# P08_PHY_3.net
KiCad netlist of a schematic drawn in Altium Designer
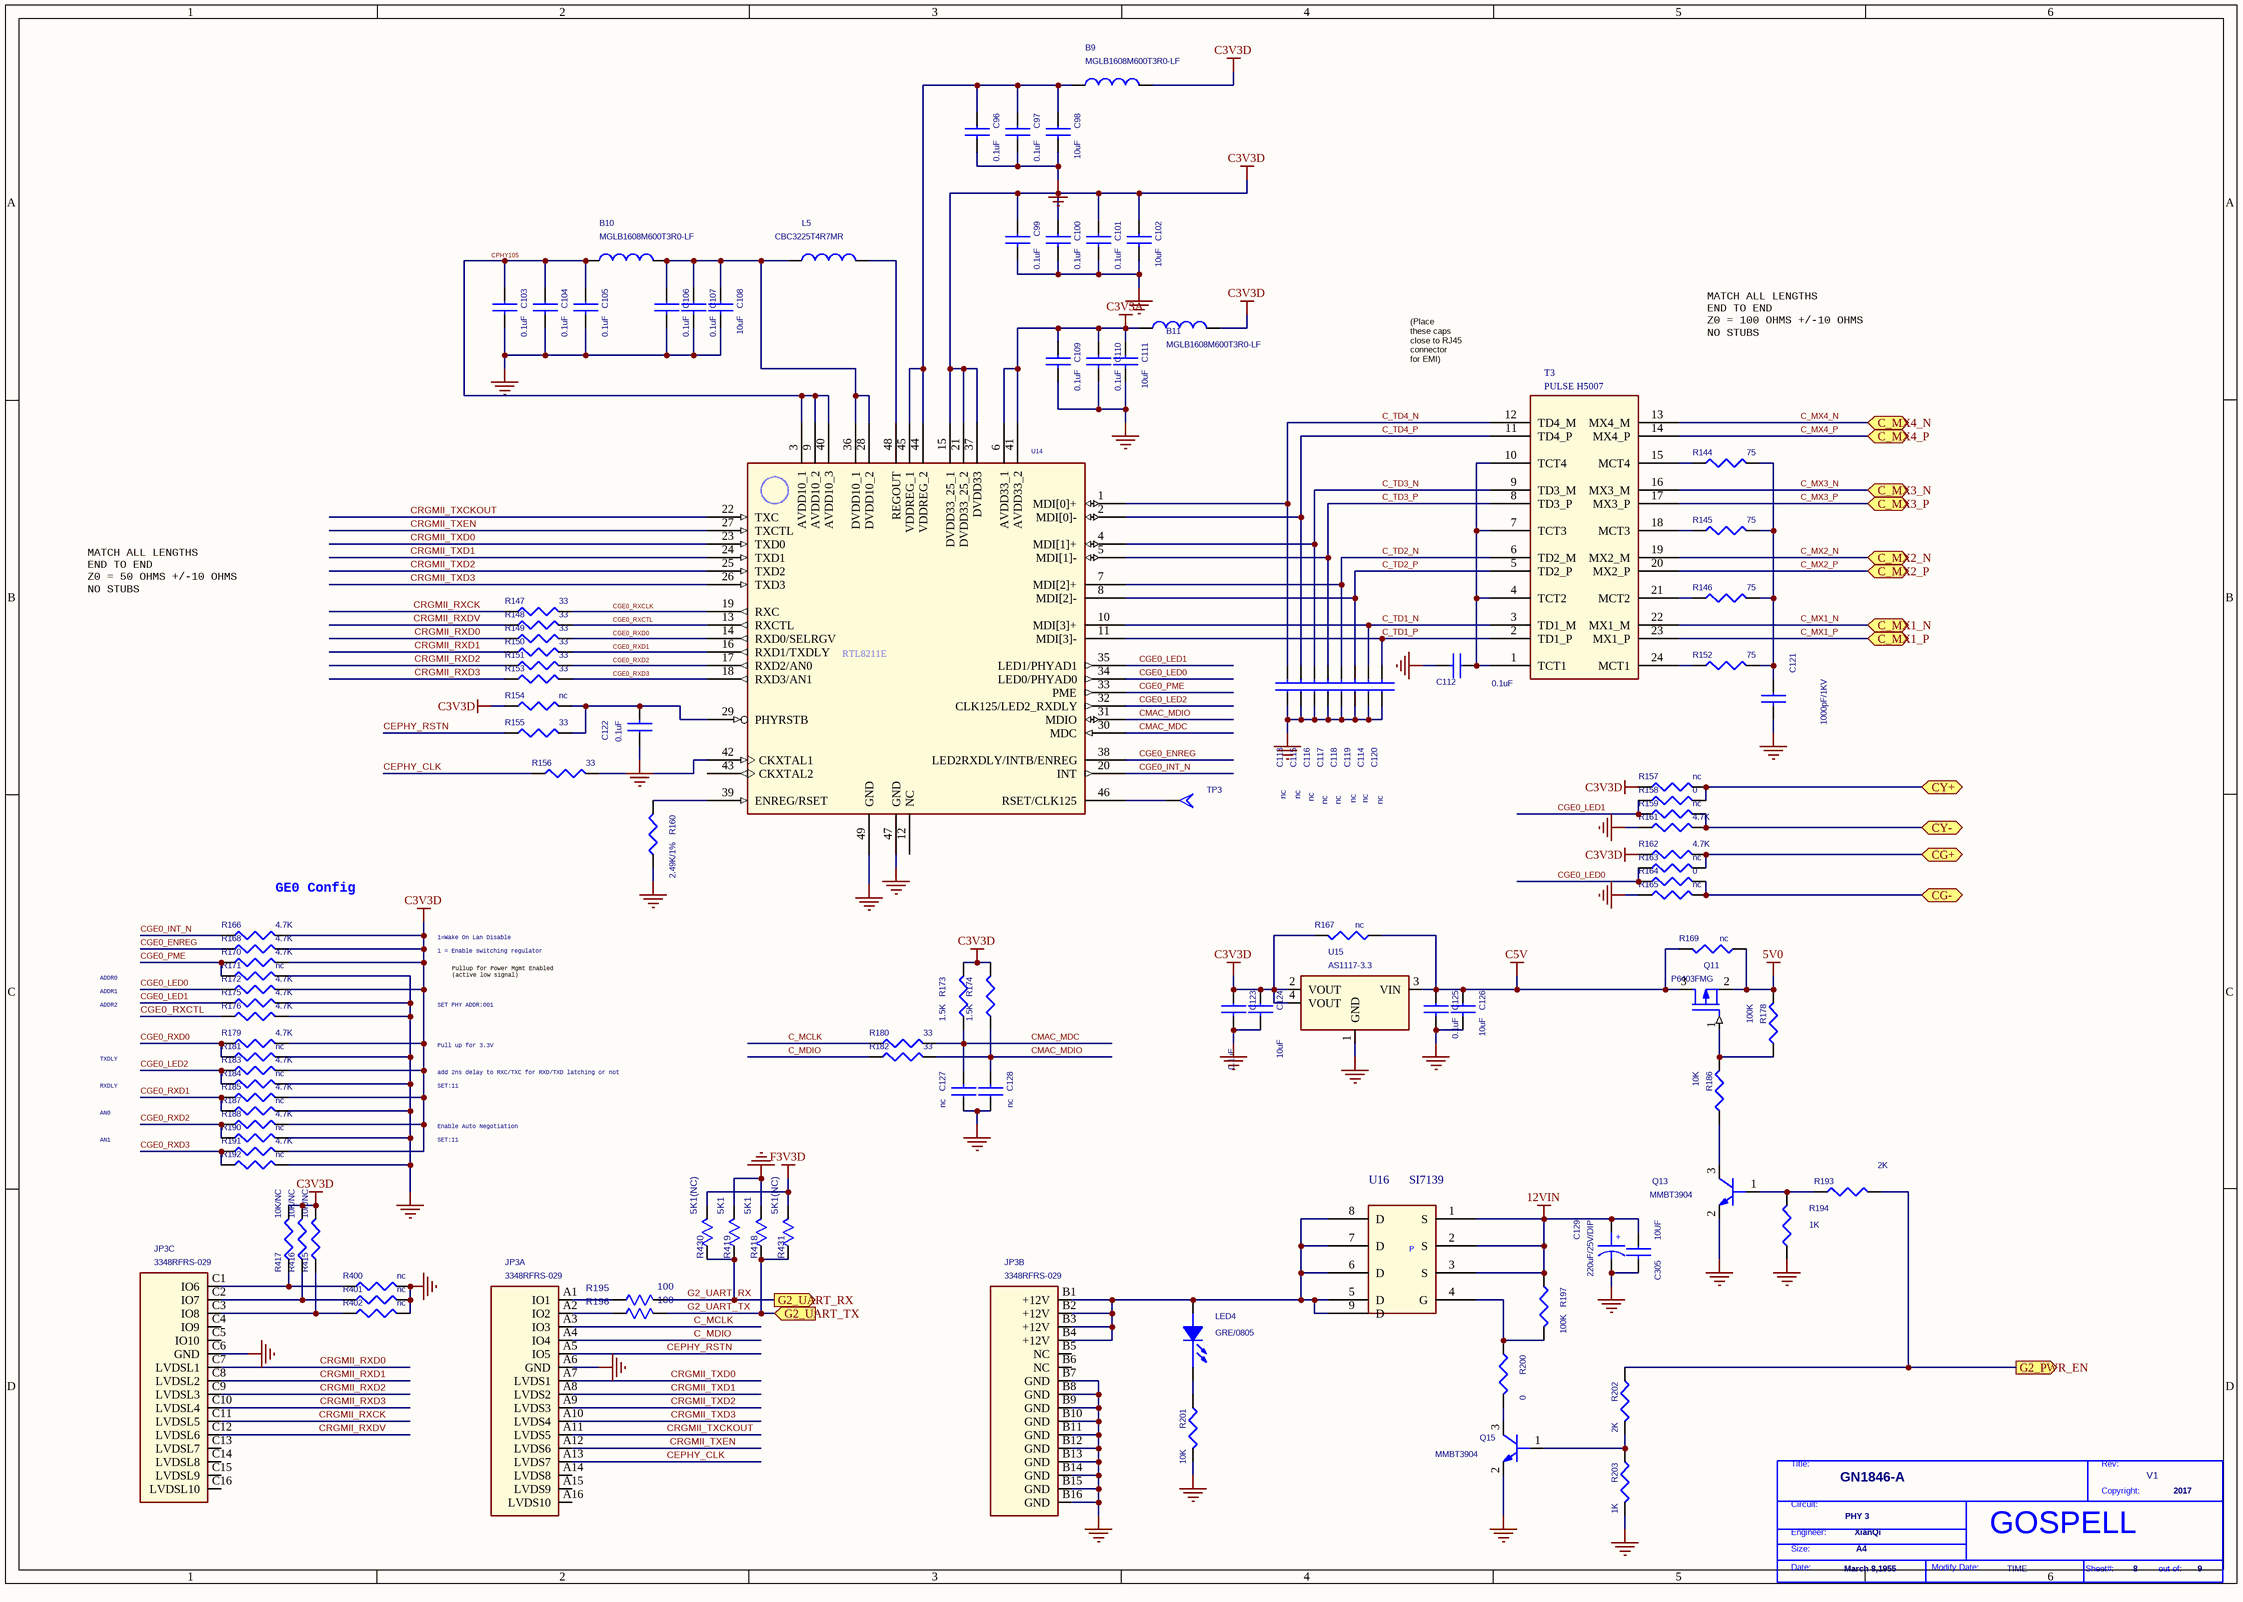
[diagram p0: P08 PHY 3.SchDoc]

(export (version "E")
  (design (tool "Eeschema 10.0.6"))
  (components
    (comp (ref "B9") (value "MGLB1608M600T3R0-LF") (libsource (lib "*") (part "CHOKE TORROID_0")))
    (comp (ref "B10") (value "MGLB1608M600T3R0-LF") (libsource (lib "*") (part "CHOKE TORROID_0")))
    (comp (ref "B11") (value "MGLB1608M600T3R0-LF") (libsource (lib "*") (part "CHOKE TORROID_0")))
    (comp (ref "C96") (value "0.1uF") (libsource (lib "*") (part "CAP NP_Dup1")))
    (comp (ref "C97") (value "0.1uF") (libsource (lib "*") (part "CAP NP_Dup1")))
    (comp (ref "C98") (value "10uF") (libsource (lib "*") (part "CAP NP_Dup1")))
    (comp (ref "C99") (value "0.1uF") (libsource (lib "*") (part "CAP NP_Dup1")))
    (comp (ref "C100") (value "0.1uF") (libsource (lib "*") (part "CAP NP_Dup1")))
    (comp (ref "C101") (value "0.1uF") (libsource (lib "*") (part "CAP NP_Dup1")))
    (comp (ref "C102") (value "10uF") (libsource (lib "*") (part "CAP NP_Dup1")))
    (comp (ref "C103") (value "0.1uF") (libsource (lib "*") (part "CAP NP_Dup1")))
    (comp (ref "C104") (value "0.1uF") (libsource (lib "*") (part "CAP NP_Dup1")))
    (comp (ref "C105") (value "0.1uF") (libsource (lib "*") (part "CAP NP_Dup1")))
    (comp (ref "C106") (value "0.1uF") (libsource (lib "*") (part "CAP NP_Dup1")))
    (comp (ref "C107") (value "0.1uF") (libsource (lib "*") (part "CAP NP_Dup1")))
    (comp (ref "C108") (value "10uF") (libsource (lib "*") (part "CAP NP_Dup1")))
    (comp (ref "C109") (value "0.1uF") (libsource (lib "*") (part "CAP NP_Dup1")))
    (comp (ref "C110") (value "0.1uF") (libsource (lib "*") (part "CAP NP_Dup1")))
    (comp (ref "C111") (value "10uF") (libsource (lib "*") (part "CAP NP_Dup1")))
    (comp (ref "C112") (value "0.1uF") (libsource (lib "*") (part "CAP NP_Dup1")))
    (comp (ref "C113") (value "nc") (libsource (lib "*") (part "CAP NP_Dup1")))
    (comp (ref "C114") (value "nc") (libsource (lib "*") (part "CAP NP_Dup1")))
    (comp (ref "C115") (value "nc") (libsource (lib "*") (part "CAP NP_Dup1")))
    (comp (ref "C116") (value "nc") (libsource (lib "*") (part "CAP NP_Dup1")))
    (comp (ref "C117") (value "nc") (libsource (lib "*") (part "CAP NP_Dup1")))
    (comp (ref "C118") (value "nc") (libsource (lib "*") (part "CAP NP_Dup1")))
    (comp (ref "C119") (value "nc") (libsource (lib "*") (part "CAP NP_Dup1")))
    (comp (ref "C120") (value "nc") (libsource (lib "*") (part "CAP NP_Dup1")))
    (comp (ref "C121") (value "1000pF/1KV") (libsource (lib "*") (part "CAP NP_Dup1")))
    (comp (ref "C122") (value "0.1uF") (libsource (lib "*") (part "CAP NP_Dup1")))
    (comp (ref "C123") (value "0.1uF") (libsource (lib "*") (part "CAP NP_Dup1")))
    (comp (ref "C124") (value "10uF") (libsource (lib "*") (part "CAP NP_Dup1")))
    (comp (ref "C125") (value "0.1uF") (libsource (lib "*") (part "CAP NP_Dup1")))
    (comp (ref "C126") (value "10uF") (libsource (lib "*") (part "CAP NP_Dup1")))
    (comp (ref "C127") (value "nc") (libsource (lib "*") (part "CAP NP_Dup1")))
    (comp (ref "C128") (value "nc") (libsource (lib "*") (part "CAP NP_Dup1")))
    (comp (ref "C129") (value "220uF/25V/DIP") (libsource (lib "*") (part "CAP POL")))
    (comp (ref "C305") (value "10UF") (libsource (lib "*") (part "CAP NP")))
    (comp (ref "JP3")
      (value "3348RFRS-029")
      (footprint "3348RFRS-029")
      (libsource (lib "*") (part "3348RFRS-029"))
    )
    (comp (ref "L5") (value "CBC3225T4R7MR") (libsource (lib "*") (part "CHOKE TORROID_0")))
    (comp (ref "LED4") (value "GRE/0805") (libsource (lib "*") (part "LED_0")))
    (comp (ref "Q11") (value "P6403FMG") (libsource (lib "*") (part "MOSFET P_0")))
    (comp (ref "Q13") (value "MMBT3904") (footprint "SOT23") (libsource (lib "*") (part "2N3904")))
    (comp (ref "Q15") (value "MMBT3904") (footprint "SOT23") (libsource (lib "*") (part "2N3904")))
    (comp (ref "R144") (value "75") (libsource (lib "*") (part "R_Dup1")))
    (comp (ref "R145") (value "75") (libsource (lib "*") (part "R_Dup1")))
    (comp (ref "R146") (value "75") (libsource (lib "*") (part "R_Dup1")))
    (comp (ref "R147") (value "33") (libsource (lib "*") (part "R_Dup1")))
    (comp (ref "R148") (value "33") (libsource (lib "*") (part "R_Dup1")))
    (comp (ref "R149") (value "33") (libsource (lib "*") (part "R_Dup1")))
    (comp (ref "R150") (value "33") (libsource (lib "*") (part "R_Dup1")))
    (comp (ref "R151") (value "33") (libsource (lib "*") (part "R_Dup1")))
    (comp (ref "R152") (value "75") (libsource (lib "*") (part "R_Dup1")))
    (comp (ref "R153") (value "33") (libsource (lib "*") (part "R_Dup1")))
    (comp (ref "R154") (value "nc") (libsource (lib "*") (part "R_Dup1")))
    (comp (ref "R155") (value "33") (libsource (lib "*") (part "R_Dup1")))
    (comp (ref "R156") (value "33") (libsource (lib "*") (part "R_Dup1")))
    (comp (ref "R157") (value "nc") (libsource (lib "*") (part "R_Dup1")))
    (comp (ref "R158") (value "0") (libsource (lib "*") (part "R_Dup1")))
    (comp (ref "R159") (value "nc") (libsource (lib "*") (part "R_Dup1")))
    (comp (ref "R160") (value "2.49K/1%") (libsource (lib "*") (part "R_Dup1")))
    (comp (ref "R161") (value "4.7K") (libsource (lib "*") (part "R_Dup1")))
    (comp (ref "R162") (value "4.7K") (libsource (lib "*") (part "R_Dup1")))
    (comp (ref "R163") (value "nc") (libsource (lib "*") (part "R_Dup1")))
    (comp (ref "R164") (value "0") (libsource (lib "*") (part "R_Dup1")))
    (comp (ref "R165") (value "nc") (libsource (lib "*") (part "R_Dup1")))
    (comp (ref "R166") (value "4.7K") (libsource (lib "*") (part "R_Dup1")))
    (comp (ref "R167") (value "nc") (libsource (lib "*") (part "R")))
    (comp (ref "R168") (value "4.7K") (libsource (lib "*") (part "R_Dup1")))
    (comp (ref "R169") (value "nc") (libsource (lib "*") (part "R")))
    (comp (ref "R170") (value "4.7K") (libsource (lib "*") (part "R_Dup1")))
    (comp (ref "R171") (value "nc") (libsource (lib "*") (part "R_Dup1")))
    (comp (ref "R172") (value "4.7K") (libsource (lib "*") (part "R_Dup1")))
    (comp (ref "R173") (value "1.5K") (libsource (lib "*") (part "R_Dup1")))
    (comp (ref "R174") (value "1.5K") (libsource (lib "*") (part "R_Dup1")))
    (comp (ref "R175") (value "4.7K") (libsource (lib "*") (part "R_Dup1")))
    (comp (ref "R176") (value "4.7K") (libsource (lib "*") (part "R_Dup1")))
    (comp (ref "R178") (value "100K") (libsource (lib "*") (part "R")))
    (comp (ref "R179") (value "4.7K") (libsource (lib "*") (part "R_Dup1")))
    (comp (ref "R180") (value "33") (libsource (lib "*") (part "R_Dup1")))
    (comp (ref "R181") (value "nc") (libsource (lib "*") (part "R_Dup1")))
    (comp (ref "R182") (value "33") (libsource (lib "*") (part "R_Dup1")))
    (comp (ref "R183") (value "4.7K") (libsource (lib "*") (part "R_Dup1")))
    (comp (ref "R184") (value "nc") (libsource (lib "*") (part "R_Dup1")))
    (comp (ref "R185") (value "4.7K") (libsource (lib "*") (part "R_Dup1")))
    (comp (ref "R186") (value "10K") (libsource (lib "*") (part "R")))
    (comp (ref "R187") (value "nc") (libsource (lib "*") (part "R_Dup1")))
    (comp (ref "R188") (value "4.7K") (libsource (lib "*") (part "R_Dup1")))
    (comp (ref "R190") (value "nc") (libsource (lib "*") (part "R_Dup1")))
    (comp (ref "R191") (value "4.7K") (libsource (lib "*") (part "R_Dup1")))
    (comp (ref "R192") (value "nc") (libsource (lib "*") (part "R_Dup1")))
    (comp (ref "R193") (value "2K") (libsource (lib "*") (part "R")))
    (comp (ref "R194") (value "1K") (libsource (lib "*") (part "R")))
    (comp (ref "R195") (value "100") (libsource (lib "*") (part "R_1")))
    (comp (ref "R196") (value "100") (libsource (lib "*") (part "R_1")))
    (comp (ref "R197") (value "100K") (libsource (lib "*") (part "R_Dup1")))
    (comp (ref "R200") (value "0") (libsource (lib "*") (part "R_Dup1")))
    (comp (ref "R201") (value "10K") (libsource (lib "*") (part "R_Dup1")))
    (comp (ref "R202") (value "2K") (libsource (lib "*") (part "R_Dup1")))
    (comp (ref "R203") (value "1K") (libsource (lib "*") (part "R_Dup1")))
    (comp (ref "R400") (value "nc") (libsource (lib "*") (part "R_Dup1")))
    (comp (ref "R401") (value "nc") (libsource (lib "*") (part "R_Dup1")))
    (comp (ref "R402") (value "nc") (libsource (lib "*") (part "R_Dup1")))
    (comp (ref "R415") (value "10K/NC") (libsource (lib "*") (part "R_Dup1")))
    (comp (ref "R416") (value "10K/NC") (libsource (lib "*") (part "R_Dup1")))
    (comp (ref "R417") (value "10K/NC") (libsource (lib "*") (part "R_Dup1")))
    (comp (ref "R418") (value "5K1") (libsource (lib "*") (part "R_1")))
    (comp (ref "R419") (value "5K1") (libsource (lib "*") (part "R_1")))
    (comp (ref "R430") (value "5K1(NC)") (libsource (lib "*") (part "R_1")))
    (comp (ref "R431") (value "5K1(NC)") (libsource (lib "*") (part "R_1")))
    (comp (ref "T3") (value "PULSE H5007") (footprint "H5007-H") (libsource (lib "*") (part "PULSE H5007_0")))
    (comp (ref "TP3") (value "T POINT A") (libsource (lib "*") (part "T POINT A")))
    (comp (ref "U14")
      (value "RTL8211D")
      (footprint "QFN-48P-RTL8211")
      (libsource (lib "*") (part "RTL8211D_1"))
    )
    (comp (ref "U15") (value "AS1117-3.3") (footprint "SOT223") (libsource (lib "*") (part "AS1117-X_2")))
    (comp (ref "U16")
      (value "SI7139")
      (footprint "PowerPAKSO8")
      (libsource (lib "GN-1846-A-V1_Library") (part "SI7139"))
    )
  )
  (nets
    (net (code "1") (name "/CEPHY_CLK") (class "Default")
      (node (ref "JP3") (pin "A13") (pinfunction "LVDS7_A13") (pintype "passive"))
      (node (ref "R156") (pin "1") (pinfunction "1_1") (pintype "passive"))
    )
    (net (code "2") (name "/CEPHY_RSTN") (class "Default")
      (node (ref "JP3") (pin "A5") (pinfunction "IO5_A5") (pintype "passive"))
      (node (ref "R155") (pin "1") (pinfunction "1_1") (pintype "passive"))
    )
    (net (code "3") (name "/CG+") (class "Default")
      (node (ref "R162") (pin "2") (pinfunction "2_2") (pintype "passive"))
      (node (ref "R163") (pin "2") (pinfunction "2_2") (pintype "passive"))
    )
    (net (code "4") (name "/CG-") (class "Default")
      (node (ref "R164") (pin "2") (pinfunction "2_2") (pintype "passive"))
      (node (ref "R165") (pin "2") (pinfunction "2_2") (pintype "passive"))
    )
    (net (code "5") (name "/CGE0_ENREG") (class "Default")
      (node (ref "R168") (pin "1") (pinfunction "1_1") (pintype "passive"))
      (node (ref "U14") (pin "38") (pinfunction "LED2RXDLY/INTB/ENREG_38") (pintype "passive"))
    )
    (net (code "6") (name "/CGE0_INT_N") (class "Default")
      (node (ref "R166") (pin "1") (pinfunction "1_1") (pintype "passive"))
      (node (ref "U14") (pin "20") (pinfunction "INT_20") (pintype "output"))
    )
    (net (code "7") (name "/CGE0_LED0") (class "Default")
      (node (ref "R163") (pin "1") (pinfunction "1_1") (pintype "passive"))
      (node (ref "R164") (pin "1") (pinfunction "1_1") (pintype "passive"))
      (node (ref "R172") (pin "1") (pinfunction "1_1") (pintype "passive"))
      (node (ref "U14") (pin "34") (pinfunction "LED0/PHYAD0_34") (pintype "output"))
    )
    (net (code "8") (name "/CGE0_LED1") (class "Default")
      (node (ref "R158") (pin "1") (pinfunction "1_1") (pintype "passive"))
      (node (ref "R159") (pin "1") (pinfunction "1_1") (pintype "passive"))
      (node (ref "R175") (pin "1") (pinfunction "1_1") (pintype "passive"))
      (node (ref "U14") (pin "35") (pinfunction "LED1/PHYAD1_35") (pintype "output"))
    )
    (net (code "9") (name "/CGE0_LED2") (class "Default")
      (node (ref "R183") (pin "1") (pinfunction "1_1") (pintype "passive"))
      (node (ref "R184") (pin "1") (pinfunction "1_1") (pintype "passive"))
      (node (ref "U14") (pin "32") (pinfunction "CLK125/LED2_RXDLY_32") (pintype "output"))
    )
    (net (code "10") (name "/CGE0_PME") (class "Default")
      (node (ref "R170") (pin "1") (pinfunction "1_1") (pintype "passive"))
      (node (ref "R171") (pin "1") (pinfunction "1_1") (pintype "passive"))
      (node (ref "U14") (pin "33") (pinfunction "PME_33") (pintype "output"))
    )
    (net (code "11") (name "/CGE0_RXCLK") (class "Default")
      (node (ref "R147") (pin "2") (pinfunction "2_2") (pintype "passive"))
      (node (ref "U14") (pin "19") (pinfunction "RXC_19") (pintype "output"))
    )
    (net (code "12") (name "/CGE0_RXCTL") (class "Default")
      (node (ref "R148") (pin "2") (pinfunction "2_2") (pintype "passive"))
      (node (ref "R176") (pin "1") (pinfunction "1_1") (pintype "passive"))
      (node (ref "U14") (pin "13") (pinfunction "RXCTL_13") (pintype "output"))
    )
    (net (code "13") (name "/CGE0_RXD0") (class "Default")
      (node (ref "R149") (pin "2") (pinfunction "2_2") (pintype "passive"))
      (node (ref "R179") (pin "1") (pinfunction "1_1") (pintype "passive"))
      (node (ref "R181") (pin "1") (pinfunction "1_1") (pintype "passive"))
      (node (ref "U14") (pin "14") (pinfunction "RXD0/SELRGV_14") (pintype "output"))
    )
    (net (code "14") (name "/CGE0_RXD1") (class "Default")
      (node (ref "R150") (pin "2") (pinfunction "2_2") (pintype "passive"))
      (node (ref "R185") (pin "1") (pinfunction "1_1") (pintype "passive"))
      (node (ref "R187") (pin "1") (pinfunction "1_1") (pintype "passive"))
      (node (ref "U14") (pin "16") (pinfunction "RXD1/TXDLY_16") (pintype "output"))
    )
    (net (code "15") (name "/CGE0_RXD2") (class "Default")
      (node (ref "R151") (pin "2") (pinfunction "2_2") (pintype "passive"))
      (node (ref "R188") (pin "1") (pinfunction "1_1") (pintype "passive"))
      (node (ref "R190") (pin "1") (pinfunction "1_1") (pintype "passive"))
      (node (ref "U14") (pin "17") (pinfunction "RXD2/AN0_17") (pintype "output"))
    )
    (net (code "16") (name "/CGE0_RXD3") (class "Default")
      (node (ref "R153") (pin "2") (pinfunction "2_2") (pintype "passive"))
      (node (ref "R191") (pin "1") (pinfunction "1_1") (pintype "passive"))
      (node (ref "R192") (pin "1") (pinfunction "1_1") (pintype "passive"))
      (node (ref "U14") (pin "18") (pinfunction "RXD3/AN1_18") (pintype "output"))
    )
    (net (code "17") (name "/CMAC_MDC") (class "Default")
      (node (ref "C127") (pin "2") (pinfunction "2_2") (pintype "passive"))
      (node (ref "R173") (pin "1") (pinfunction "1_1") (pintype "passive"))
      (node (ref "R180") (pin "2") (pinfunction "2_2") (pintype "passive"))
      (node (ref "U14") (pin "30") (pinfunction "MDC_30") (pintype "input"))
    )
    (net (code "18") (name "/CMAC_MDIO") (class "Default")
      (node (ref "C128") (pin "2") (pinfunction "2_2") (pintype "passive"))
      (node (ref "R174") (pin "1") (pinfunction "1_1") (pintype "passive"))
      (node (ref "R182") (pin "2") (pinfunction "2_2") (pintype "passive"))
      (node (ref "U14") (pin "31") (pinfunction "MDIO_31") (pintype "bidirectional"))
    )
    (net (code "19") (name "/CPHY105") (class "Default")
      (node (ref "B10") (pin "1") (pinfunction "1_1") (pintype "passive"))
      (node (ref "C103") (pin "1") (pinfunction "1_1") (pintype "passive"))
      (node (ref "C104") (pin "1") (pinfunction "1_1") (pintype "passive"))
      (node (ref "C105") (pin "1") (pinfunction "1_1") (pintype "passive"))
      (node (ref "U14") (pin "3") (pinfunction "AVDD10_1_3") (pintype "power_in"))
      (node (ref "U14") (pin "40") (pinfunction "AVDD10_3_40") (pintype "power_in"))
      (node (ref "U14") (pin "9") (pinfunction "AVDD10_2_9") (pintype "power_in"))
    )
    (net (code "20") (name "/CRGMII_RXCK") (class "Default")
      (node (ref "JP3") (pin "C11") (pinfunction "LVDSL5_C11") (pintype "passive"))
      (node (ref "R147") (pin "1") (pinfunction "1_1") (pintype "passive"))
    )
    (net (code "21") (name "/CRGMII_RXD0") (class "Default")
      (node (ref "JP3") (pin "C7") (pinfunction "LVDSL1_C7") (pintype "passive"))
      (node (ref "R149") (pin "1") (pinfunction "1_1") (pintype "passive"))
    )
    (net (code "22") (name "/CRGMII_RXD1") (class "Default")
      (node (ref "JP3") (pin "C8") (pinfunction "LVDSL2_C8") (pintype "passive"))
      (node (ref "R150") (pin "1") (pinfunction "1_1") (pintype "passive"))
    )
    (net (code "23") (name "/CRGMII_RXD2") (class "Default")
      (node (ref "JP3") (pin "C9") (pinfunction "LVDSL3_C9") (pintype "passive"))
      (node (ref "R151") (pin "1") (pinfunction "1_1") (pintype "passive"))
    )
    (net (code "24") (name "/CRGMII_RXD3") (class "Default")
      (node (ref "JP3") (pin "C10") (pinfunction "LVDSL4_C10") (pintype "passive"))
      (node (ref "R153") (pin "1") (pinfunction "1_1") (pintype "passive"))
    )
    (net (code "25") (name "/CRGMII_RXDV") (class "Default")
      (node (ref "JP3") (pin "C12") (pinfunction "LVDSL6_C12") (pintype "passive"))
      (node (ref "R148") (pin "1") (pinfunction "1_1") (pintype "passive"))
    )
    (net (code "26") (name "/CRGMII_TXCKOUT") (class "Default")
      (node (ref "JP3") (pin "A11") (pinfunction "LVDS5_A11") (pintype "passive"))
      (node (ref "U14") (pin "22") (pinfunction "TXC_22") (pintype "input"))
    )
    (net (code "27") (name "/CRGMII_TXD0") (class "Default")
      (node (ref "JP3") (pin "A7") (pinfunction "LVDS1_A7") (pintype "passive"))
      (node (ref "U14") (pin "23") (pinfunction "TXD0_23") (pintype "input"))
    )
    (net (code "28") (name "/CRGMII_TXD1") (class "Default")
      (node (ref "JP3") (pin "A8") (pinfunction "LVDS2_A8") (pintype "passive"))
      (node (ref "U14") (pin "24") (pinfunction "TXD1_24") (pintype "input"))
    )
    (net (code "29") (name "/CRGMII_TXD2") (class "Default")
      (node (ref "JP3") (pin "A9") (pinfunction "LVDS3_A9") (pintype "passive"))
      (node (ref "U14") (pin "25") (pinfunction "TXD2_25") (pintype "input"))
    )
    (net (code "30") (name "/CRGMII_TXD3") (class "Default")
      (node (ref "JP3") (pin "A10") (pinfunction "LVDS4_A10") (pintype "passive"))
      (node (ref "U14") (pin "26") (pinfunction "TXD3_26") (pintype "input"))
    )
    (net (code "31") (name "/CRGMII_TXEN") (class "Default")
      (node (ref "JP3") (pin "A12") (pinfunction "LVDS6_A12") (pintype "passive"))
      (node (ref "U14") (pin "27") (pinfunction "TXCTL_27") (pintype "input"))
    )
    (net (code "32") (name "/CY+") (class "Default")
      (node (ref "R157") (pin "2") (pinfunction "2_2") (pintype "passive"))
      (node (ref "R158") (pin "2") (pinfunction "2_2") (pintype "passive"))
    )
    (net (code "33") (name "/CY-") (class "Default")
      (node (ref "R159") (pin "2") (pinfunction "2_2") (pintype "passive"))
      (node (ref "R161") (pin "2") (pinfunction "2_2") (pintype "passive"))
    )
    (net (code "34") (name "/C_MCLK") (class "Default")
      (node (ref "JP3") (pin "A3") (pinfunction "IO3_A3") (pintype "passive"))
      (node (ref "R180") (pin "1") (pinfunction "1_1") (pintype "passive"))
    )
    (net (code "35") (name "/C_MDIO") (class "Default")
      (node (ref "JP3") (pin "A4") (pinfunction "IO4_A4") (pintype "passive"))
      (node (ref "R182") (pin "1") (pinfunction "1_1") (pintype "passive"))
    )
    (net (code "36") (name "/C_MX1_N") (class "Default")
      (node (ref "T3") (pin "22") (pinfunction "MX1_M_22") (pintype "passive"))
    )
    (net (code "37") (name "/C_MX1_P") (class "Default")
      (node (ref "T3") (pin "23") (pinfunction "MX1_P_23") (pintype "passive"))
    )
    (net (code "38") (name "/C_MX2_N") (class "Default")
      (node (ref "T3") (pin "19") (pinfunction "MX2_M_19") (pintype "passive"))
    )
    (net (code "39") (name "/C_MX2_P") (class "Default")
      (node (ref "T3") (pin "20") (pinfunction "MX2_P_20") (pintype "passive"))
    )
    (net (code "40") (name "/C_MX3_N") (class "Default")
      (node (ref "T3") (pin "16") (pinfunction "MX3_M_16") (pintype "passive"))
    )
    (net (code "41") (name "/C_MX3_P") (class "Default")
      (node (ref "T3") (pin "17") (pinfunction "MX3_P_17") (pintype "passive"))
    )
    (net (code "42") (name "/C_MX4_N") (class "Default")
      (node (ref "T3") (pin "13") (pinfunction "MX4_M_13") (pintype "passive"))
    )
    (net (code "43") (name "/C_MX4_P") (class "Default")
      (node (ref "T3") (pin "14") (pinfunction "MX4_P_14") (pintype "passive"))
    )
    (net (code "44") (name "/C_TD1_N") (class "Default")
      (node (ref "C114") (pin "2") (pinfunction "2_2") (pintype "passive"))
      (node (ref "T3") (pin "3") (pinfunction "TD1_M_3") (pintype "passive"))
      (node (ref "U14") (pin "10") (pinfunction "MDI[3]+_10") (pintype "passive"))
    )
    (net (code "45") (name "/C_TD1_P") (class "Default")
      (node (ref "C120") (pin "2") (pinfunction "2_2") (pintype "passive"))
      (node (ref "T3") (pin "2") (pinfunction "TD1_P_2") (pintype "passive"))
      (node (ref "U14") (pin "11") (pinfunction "MDI[3]-_11") (pintype "passive"))
    )
    (net (code "46") (name "/C_TD2_N") (class "Default")
      (node (ref "C118") (pin "2") (pinfunction "2_2") (pintype "passive"))
      (node (ref "T3") (pin "6") (pinfunction "TD2_M_6") (pintype "passive"))
      (node (ref "U14") (pin "7") (pinfunction "MDI[2]+_7") (pintype "passive"))
    )
    (net (code "47") (name "/C_TD2_P") (class "Default")
      (node (ref "C119") (pin "2") (pinfunction "2_2") (pintype "passive"))
      (node (ref "T3") (pin "5") (pinfunction "TD2_P_5") (pintype "passive"))
      (node (ref "U14") (pin "8") (pinfunction "MDI[2]-_8") (pintype "passive"))
    )
    (net (code "48") (name "/C_TD3_N") (class "Default")
      (node (ref "C116") (pin "2") (pinfunction "2_2") (pintype "passive"))
      (node (ref "T3") (pin "9") (pinfunction "TD3_M_9") (pintype "passive"))
      (node (ref "U14") (pin "4") (pinfunction "MDI[1]+_4") (pintype "bidirectional"))
    )
    (net (code "49") (name "/C_TD3_P") (class "Default")
      (node (ref "C117") (pin "2") (pinfunction "2_2") (pintype "passive"))
      (node (ref "T3") (pin "8") (pinfunction "TD3_P_8") (pintype "passive"))
      (node (ref "U14") (pin "5") (pinfunction "MDI[1]-_5") (pintype "bidirectional"))
    )
    (net (code "50") (name "/C_TD4_N") (class "Default")
      (node (ref "C113") (pin "2") (pinfunction "2_2") (pintype "passive"))
      (node (ref "T3") (pin "12") (pinfunction "TD4_M_12") (pintype "passive"))
      (node (ref "U14") (pin "1") (pinfunction "MDI[0]+_1") (pintype "bidirectional"))
    )
    (net (code "51") (name "/C_TD4_P") (class "Default")
      (node (ref "C115") (pin "2") (pinfunction "2_2") (pintype "passive"))
      (node (ref "T3") (pin "11") (pinfunction "TD4_P_11") (pintype "passive"))
      (node (ref "U14") (pin "2") (pinfunction "MDI[0]-_2") (pintype "bidirectional"))
    )
    (net (code "52") (name "/G2_PWR_EN") (class "Default")
      (node (ref "R193") (pin "2") (pinfunction "2_2") (pintype "passive"))
      (node (ref "R202") (pin "2") (pinfunction "2_2") (pintype "passive"))
    )
    (net (code "53") (name "/G2_UART_RX") (class "Default")
      (node (ref "R195") (pin "2") (pinfunction "B_2") (pintype "passive"))
      (node (ref "R419") (pin "1") (pinfunction "A_1") (pintype "passive"))
      (node (ref "R430") (pin "1") (pinfunction "A_1") (pintype "passive"))
    )
    (net (code "54") (name "/G2_UART_TX") (class "Default")
      (node (ref "R196") (pin "2") (pinfunction "B_2") (pintype "passive"))
      (node (ref "R418") (pin "1") (pinfunction "A_1") (pintype "passive"))
      (node (ref "R431") (pin "1") (pinfunction "A_1") (pintype "passive"))
    )
    (net (code "55") (name "5V0") (class "Default")
      (node (ref "Q11") (pin "2") (pinfunction "SOURCE_2") (pintype "passive"))
      (node (ref "R169") (pin "2") (pinfunction "2_2") (pintype "passive"))
      (node (ref "R178") (pin "1") (pinfunction "1_1") (pintype "passive"))
    )
    (net (code "56") (name "12VIN") (class "Default")
      (node (ref "C129") (pin "1") (pinfunction "1_1") (pintype "passive"))
      (node (ref "C305") (pin "1") (pinfunction "1_1") (pintype "passive"))
      (node (ref "R197") (pin "2") (pinfunction "2_2") (pintype "passive"))
      (node (ref "U16") (pin "1") (pinfunction "S_1") (pintype "passive"))
      (node (ref "U16") (pin "2") (pinfunction "S_2") (pintype "passive"))
      (node (ref "U16") (pin "3") (pinfunction "S_3") (pintype "passive"))
    )
    (net (code "57") (name "C3V3A") (class "Default")
      (node (ref "B11") (pin "1") (pinfunction "1_1") (pintype "passive"))
      (node (ref "C109") (pin "1") (pinfunction "1_1") (pintype "passive"))
      (node (ref "C110") (pin "1") (pinfunction "1_1") (pintype "passive"))
      (node (ref "C111") (pin "1") (pinfunction "1_1") (pintype "passive"))
      (node (ref "U14") (pin "41") (pinfunction "AVDD33_2_41") (pintype "power_in"))
      (node (ref "U14") (pin "6") (pinfunction "AVDD33_1_6") (pintype "power_in"))
    )
    (net (code "58") (name "C3V3D") (class "Default")
      (node (ref "B11") (pin "2") (pinfunction "2_2") (pintype "passive"))
      (node (ref "B9") (pin "2") (pinfunction "2_2") (pintype "passive"))
      (node (ref "C100") (pin "1") (pinfunction "1_1") (pintype "passive"))
      (node (ref "C101") (pin "1") (pinfunction "1_1") (pintype "passive"))
      (node (ref "C102") (pin "1") (pinfunction "1_1") (pintype "passive"))
      (node (ref "C123") (pin "1") (pinfunction "1_1") (pintype "passive"))
      (node (ref "C124") (pin "1") (pinfunction "1_1") (pintype "passive"))
      (node (ref "C99") (pin "1") (pinfunction "1_1") (pintype "passive"))
      (node (ref "R154") (pin "1") (pinfunction "1_1") (pintype "passive"))
      (node (ref "R157") (pin "1") (pinfunction "1_1") (pintype "passive"))
      (node (ref "R162") (pin "1") (pinfunction "1_1") (pintype "passive"))
      (node (ref "R166") (pin "2") (pinfunction "2_2") (pintype "passive"))
      (node (ref "R167") (pin "1") (pinfunction "1_1") (pintype "passive"))
      (node (ref "R168") (pin "2") (pinfunction "2_2") (pintype "passive"))
      (node (ref "R170") (pin "2") (pinfunction "2_2") (pintype "passive"))
      (node (ref "R172") (pin "2") (pinfunction "2_2") (pintype "passive"))
      (node (ref "R173") (pin "2") (pinfunction "2_2") (pintype "passive"))
      (node (ref "R174") (pin "2") (pinfunction "2_2") (pintype "passive"))
      (node (ref "R179") (pin "2") (pinfunction "2_2") (pintype "passive"))
      (node (ref "R183") (pin "2") (pinfunction "2_2") (pintype "passive"))
      (node (ref "R185") (pin "2") (pinfunction "2_2") (pintype "passive"))
      (node (ref "R188") (pin "2") (pinfunction "2_2") (pintype "passive"))
      (node (ref "R191") (pin "2") (pinfunction "2_2") (pintype "passive"))
      (node (ref "R415") (pin "2") (pinfunction "2_2") (pintype "passive"))
      (node (ref "R416") (pin "2") (pinfunction "2_2") (pintype "passive"))
      (node (ref "R417") (pin "2") (pinfunction "2_2") (pintype "passive"))
      (node (ref "U14") (pin "15") (pinfunction "DVDD33_25_1_15") (pintype "power_in"))
      (node (ref "U14") (pin "21") (pinfunction "DVDD33_25_2_21") (pintype "power_in"))
      (node (ref "U14") (pin "37") (pinfunction "DVDD33_37") (pintype "power_in"))
      (node (ref "U15") (pin "2") (pinfunction "VOUT_2") (pintype "passive"))
      (node (ref "U15") (pin "4") (pinfunction "VOUT_4") (pintype "passive"))
    )
    (net (code "59") (name "C5V") (class "Default")
      (node (ref "C125") (pin "1") (pinfunction "1_1") (pintype "passive"))
      (node (ref "C126") (pin "1") (pinfunction "1_1") (pintype "passive"))
      (node (ref "Q11") (pin "3") (pinfunction "DRAIN_3") (pintype "passive"))
      (node (ref "R167") (pin "2") (pinfunction "2_2") (pintype "passive"))
      (node (ref "R169") (pin "1") (pinfunction "1_1") (pintype "passive"))
      (node (ref "U15") (pin "3") (pinfunction "VIN_3") (pintype "passive"))
    )
    (net (code "60") (name "F3V3D") (class "Default")
      (node (ref "R430") (pin "2") (pinfunction "B_2") (pintype "passive"))
      (node (ref "R431") (pin "2") (pinfunction "B_2") (pintype "passive"))
    )
    (net (code "61") (name "GND") (class "Default")
      (node (ref "C100") (pin "2") (pinfunction "2_2") (pintype "passive"))
      (node (ref "C101") (pin "2") (pinfunction "2_2") (pintype "passive"))
      (node (ref "C102") (pin "2") (pinfunction "2_2") (pintype "passive"))
      (node (ref "C103") (pin "2") (pinfunction "2_2") (pintype "passive"))
      (node (ref "C104") (pin "2") (pinfunction "2_2") (pintype "passive"))
      (node (ref "C105") (pin "2") (pinfunction "2_2") (pintype "passive"))
      (node (ref "C106") (pin "2") (pinfunction "2_2") (pintype "passive"))
      (node (ref "C107") (pin "2") (pinfunction "2_2") (pintype "passive"))
      (node (ref "C108") (pin "2") (pinfunction "2_2") (pintype "passive"))
      (node (ref "C109") (pin "2") (pinfunction "2_2") (pintype "passive"))
      (node (ref "C110") (pin "2") (pinfunction "2_2") (pintype "passive"))
      (node (ref "C111") (pin "2") (pinfunction "2_2") (pintype "passive"))
      (node (ref "C112") (pin "2") (pinfunction "2_2") (pintype "passive"))
      (node (ref "C113") (pin "1") (pinfunction "1_1") (pintype "passive"))
      (node (ref "C114") (pin "1") (pinfunction "1_1") (pintype "passive"))
      (node (ref "C115") (pin "1") (pinfunction "1_1") (pintype "passive"))
      (node (ref "C116") (pin "1") (pinfunction "1_1") (pintype "passive"))
      (node (ref "C117") (pin "1") (pinfunction "1_1") (pintype "passive"))
      (node (ref "C118") (pin "1") (pinfunction "1_1") (pintype "passive"))
      (node (ref "C119") (pin "1") (pinfunction "1_1") (pintype "passive"))
      (node (ref "C120") (pin "1") (pinfunction "1_1") (pintype "passive"))
      (node (ref "C121") (pin "2") (pinfunction "2_2") (pintype "passive"))
      (node (ref "C122") (pin "1") (pinfunction "1_1") (pintype "passive"))
      (node (ref "C123") (pin "2") (pinfunction "2_2") (pintype "passive"))
      (node (ref "C124") (pin "2") (pinfunction "2_2") (pintype "passive"))
      (node (ref "C125") (pin "2") (pinfunction "2_2") (pintype "passive"))
      (node (ref "C126") (pin "2") (pinfunction "2_2") (pintype "passive"))
      (node (ref "C127") (pin "1") (pinfunction "1_1") (pintype "passive"))
      (node (ref "C128") (pin "1") (pinfunction "1_1") (pintype "passive"))
      (node (ref "C129") (pin "2") (pinfunction "2_2") (pintype "passive"))
      (node (ref "C305") (pin "2") (pinfunction "2_2") (pintype "passive"))
      (node (ref "C96") (pin "2") (pinfunction "2_2") (pintype "passive"))
      (node (ref "C97") (pin "2") (pinfunction "2_2") (pintype "passive"))
      (node (ref "C98") (pin "2") (pinfunction "2_2") (pintype "passive"))
      (node (ref "C99") (pin "2") (pinfunction "2_2") (pintype "passive"))
      (node (ref "JP3") (pin "A6") (pinfunction "GND_A6") (pintype "passive"))
      (node (ref "JP3") (pin "B10") (pinfunction "GND_B10") (pintype "passive"))
      (node (ref "JP3") (pin "B11") (pinfunction "GND_B11") (pintype "passive"))
      (node (ref "JP3") (pin "B12") (pinfunction "GND_B12") (pintype "passive"))
      (node (ref "JP3") (pin "B13") (pinfunction "GND_B13") (pintype "passive"))
      (node (ref "JP3") (pin "B14") (pinfunction "GND_B14") (pintype "passive"))
      (node (ref "JP3") (pin "B15") (pinfunction "GND_B15") (pintype "passive"))
      (node (ref "JP3") (pin "B16") (pinfunction "GND_B16") (pintype "passive"))
      (node (ref "JP3") (pin "B7") (pinfunction "GND_B7") (pintype "passive"))
      (node (ref "JP3") (pin "B8") (pinfunction "GND_B8") (pintype "passive"))
      (node (ref "JP3") (pin "B9") (pinfunction "GND_B9") (pintype "passive"))
      (node (ref "JP3") (pin "C6") (pinfunction "GND_C6") (pintype "passive"))
      (node (ref "Q13") (pin "2") (pinfunction "EMITTER_2") (pintype "passive"))
      (node (ref "Q15") (pin "2") (pinfunction "EMITTER_2") (pintype "passive"))
      (node (ref "R160") (pin "1") (pinfunction "1_1") (pintype "passive"))
      (node (ref "R161") (pin "1") (pinfunction "1_1") (pintype "passive"))
      (node (ref "R165") (pin "1") (pinfunction "1_1") (pintype "passive"))
      (node (ref "R171") (pin "2") (pinfunction "2_2") (pintype "passive"))
      (node (ref "R175") (pin "2") (pinfunction "2_2") (pintype "passive"))
      (node (ref "R176") (pin "2") (pinfunction "2_2") (pintype "passive"))
      (node (ref "R181") (pin "2") (pinfunction "2_2") (pintype "passive"))
      (node (ref "R184") (pin "2") (pinfunction "2_2") (pintype "passive"))
      (node (ref "R187") (pin "2") (pinfunction "2_2") (pintype "passive"))
      (node (ref "R190") (pin "2") (pinfunction "2_2") (pintype "passive"))
      (node (ref "R192") (pin "2") (pinfunction "2_2") (pintype "passive"))
      (node (ref "R194") (pin "1") (pinfunction "1_1") (pintype "passive"))
      (node (ref "R201") (pin "1") (pinfunction "1_1") (pintype "passive"))
      (node (ref "R203") (pin "1") (pinfunction "1_1") (pintype "passive"))
      (node (ref "R400") (pin "2") (pinfunction "2_2") (pintype "passive"))
      (node (ref "R401") (pin "2") (pinfunction "2_2") (pintype "passive"))
      (node (ref "R402") (pin "2") (pinfunction "2_2") (pintype "passive"))
      (node (ref "R418") (pin "2") (pinfunction "B_2") (pintype "passive"))
      (node (ref "R419") (pin "2") (pinfunction "B_2") (pintype "passive"))
      (node (ref "U14") (pin "47") (pinfunction "GND_47") (pintype "power_in"))
      (node (ref "U14") (pin "49") (pinfunction "GND_49") (pintype "power_in"))
      (node (ref "U15") (pin "1") (pinfunction "GND_1") (pintype "passive"))
    )
    (net (code "62") (name "Net-(C121-Pad1)") (class "Default")
      (node (ref "C121") (pin "1") (pinfunction "1_1") (pintype "passive"))
      (node (ref "R144") (pin "2") (pinfunction "2_2") (pintype "passive"))
      (node (ref "R145") (pin "2") (pinfunction "2_2") (pintype "passive"))
      (node (ref "R146") (pin "2") (pinfunction "2_2") (pintype "passive"))
      (node (ref "R152") (pin "2") (pinfunction "2_2") (pintype "passive"))
    )
    (net (code "63") (name "Net-(JP3A-IO1)") (class "Default")
      (node (ref "JP3") (pin "A1") (pinfunction "IO1_A1") (pintype "passive"))
      (node (ref "R195") (pin "1") (pinfunction "A_1") (pintype "passive"))
    )
    (net (code "64") (name "Net-(JP3A-IO2)") (class "Default")
      (node (ref "JP3") (pin "A2") (pinfunction "IO2_A2") (pintype "passive"))
      (node (ref "R196") (pin "1") (pinfunction "A_1") (pintype "passive"))
    )
    (net (code "65") (name "Net-(JP3C-IO6)") (class "Default")
      (node (ref "JP3") (pin "C1") (pinfunction "IO6_C1") (pintype "passive"))
      (node (ref "R400") (pin "1") (pinfunction "1_1") (pintype "passive"))
      (node (ref "R417") (pin "1") (pinfunction "1_1") (pintype "passive"))
    )
    (net (code "66") (name "Net-(JP3C-IO7)") (class "Default")
      (node (ref "JP3") (pin "C2") (pinfunction "IO7_C2") (pintype "passive"))
      (node (ref "R401") (pin "1") (pinfunction "1_1") (pintype "passive"))
      (node (ref "R416") (pin "1") (pinfunction "1_1") (pintype "passive"))
    )
    (net (code "67") (name "Net-(JP3C-IO8)") (class "Default")
      (node (ref "JP3") (pin "C3") (pinfunction "IO8_C3") (pintype "passive"))
      (node (ref "R402") (pin "1") (pinfunction "1_1") (pintype "passive"))
      (node (ref "R415") (pin "1") (pinfunction "1_1") (pintype "passive"))
    )
    (net (code "68") (name "Net-(LED4-ANODE)") (class "Default")
      (node (ref "JP3") (pin "B1") (pinfunction "+12V_B1") (pintype "passive"))
      (node (ref "JP3") (pin "B2") (pinfunction "+12V_B2") (pintype "passive"))
      (node (ref "JP3") (pin "B3") (pinfunction "+12V_B3") (pintype "passive"))
      (node (ref "JP3") (pin "B4") (pinfunction "+12V_B4") (pintype "passive"))
      (node (ref "LED4") (pin "A") (pinfunction "ANODE_A") (pintype "passive"))
      (node (ref "U16") (pin "5") (pinfunction "D_5") (pintype "passive"))
      (node (ref "U16") (pin "6") (pinfunction "D_6") (pintype "passive"))
      (node (ref "U16") (pin "7") (pinfunction "D_7") (pintype "passive"))
      (node (ref "U16") (pin "8") (pinfunction "D_8") (pintype "passive"))
      (node (ref "U16") (pin "9") (pinfunction "D_9") (pintype "passive"))
    )
    (net (code "69") (name "Net-(LED4-CATHODE)") (class "Default")
      (node (ref "LED4") (pin "K") (pinfunction "CATHODE_K") (pintype "passive"))
      (node (ref "R201") (pin "2") (pinfunction "2_2") (pintype "passive"))
    )
    (net (code "70") (name "Net-(Q11-GATE)") (class "Default")
      (node (ref "Q11") (pin "1") (pinfunction "GATE_1") (pintype "input"))
      (node (ref "R178") (pin "2") (pinfunction "2_2") (pintype "passive"))
      (node (ref "R186") (pin "1") (pinfunction "1_1") (pintype "passive"))
    )
    (net (code "71") (name "Net-(Q13-BASE)") (class "Default")
      (node (ref "Q13") (pin "1") (pinfunction "BASE_1") (pintype "passive"))
      (node (ref "R193") (pin "1") (pinfunction "1_1") (pintype "passive"))
      (node (ref "R194") (pin "2") (pinfunction "2_2") (pintype "passive"))
    )
    (net (code "72") (name "Net-(Q13-COLLECTOR)") (class "Default")
      (node (ref "Q13") (pin "3") (pinfunction "COLLECTOR_3") (pintype "passive"))
      (node (ref "R186") (pin "2") (pinfunction "2_2") (pintype "passive"))
    )
    (net (code "73") (name "Net-(Q15-BASE)") (class "Default")
      (node (ref "Q15") (pin "1") (pinfunction "BASE_1") (pintype "passive"))
      (node (ref "R202") (pin "1") (pinfunction "1_1") (pintype "passive"))
      (node (ref "R203") (pin "2") (pinfunction "2_2") (pintype "passive"))
    )
    (net (code "74") (name "Net-(Q15-COLLECTOR)") (class "Default")
      (node (ref "Q15") (pin "3") (pinfunction "COLLECTOR_3") (pintype "passive"))
      (node (ref "R200") (pin "1") (pinfunction "1_1") (pintype "passive"))
    )
    (net (code "75") (name "Net-(T3-MCT1)") (class "Default")
      (node (ref "R152") (pin "1") (pinfunction "1_1") (pintype "passive"))
      (node (ref "T3") (pin "24") (pinfunction "MCT1_24") (pintype "passive"))
    )
    (net (code "76") (name "Net-(T3-MCT2)") (class "Default")
      (node (ref "R146") (pin "1") (pinfunction "1_1") (pintype "passive"))
      (node (ref "T3") (pin "21") (pinfunction "MCT2_21") (pintype "passive"))
    )
    (net (code "77") (name "Net-(T3-MCT3)") (class "Default")
      (node (ref "R145") (pin "1") (pinfunction "1_1") (pintype "passive"))
      (node (ref "T3") (pin "18") (pinfunction "MCT3_18") (pintype "passive"))
    )
    (net (code "78") (name "Net-(T3-MCT4)") (class "Default")
      (node (ref "R144") (pin "1") (pinfunction "1_1") (pintype "passive"))
      (node (ref "T3") (pin "15") (pinfunction "MCT4_15") (pintype "passive"))
    )
    (net (code "79") (name "Net-(T3-TCT1)") (class "Default")
      (node (ref "C112") (pin "1") (pinfunction "1_1") (pintype "passive"))
      (node (ref "T3") (pin "1") (pinfunction "TCT1_1") (pintype "passive"))
      (node (ref "T3") (pin "10") (pinfunction "TCT4_10") (pintype "passive"))
      (node (ref "T3") (pin "4") (pinfunction "TCT2_4") (pintype "passive"))
      (node (ref "T3") (pin "7") (pinfunction "TCT3_7") (pintype "passive"))
    )
    (net (code "80") (name "Net-(TP3-TP)") (class "Default")
      (node (ref "TP3") (pin "1") (pinfunction "TP_1") (pintype "passive"))
      (node (ref "U14") (pin "46") (pinfunction "RSET/CLK125_46") (pintype "passive"))
    )
    (net (code "81") (name "Net-(U14-CKXTAL1)") (class "Default")
      (node (ref "R156") (pin "2") (pinfunction "2_2") (pintype "passive"))
      (node (ref "U14") (pin "42") (pinfunction "CKXTAL1_42") (pintype "input"))
    )
    (net (code "82") (name "Net-(U14-DVDD10_1)") (class "Default")
      (node (ref "B10") (pin "2") (pinfunction "2_2") (pintype "passive"))
      (node (ref "C106") (pin "1") (pinfunction "1_1") (pintype "passive"))
      (node (ref "C107") (pin "1") (pinfunction "1_1") (pintype "passive"))
      (node (ref "C108") (pin "1") (pinfunction "1_1") (pintype "passive"))
      (node (ref "L5") (pin "1") (pinfunction "1_1") (pintype "passive"))
      (node (ref "U14") (pin "28") (pinfunction "DVDD10_2_28") (pintype "power_in"))
      (node (ref "U14") (pin "36") (pinfunction "DVDD10_1_36") (pintype "power_in"))
    )
    (net (code "83") (name "Net-(U14-ENREG{slash}RSET)") (class "Default")
      (node (ref "R160") (pin "2") (pinfunction "2_2") (pintype "passive"))
      (node (ref "U14") (pin "39") (pinfunction "ENREG/RSET_39") (pintype "input"))
    )
    (net (code "84") (name "Net-(U14-PHYRSTB)") (class "Default")
      (node (ref "C122") (pin "2") (pinfunction "2_2") (pintype "passive"))
      (node (ref "R154") (pin "2") (pinfunction "2_2") (pintype "passive"))
      (node (ref "R155") (pin "2") (pinfunction "2_2") (pintype "passive"))
      (node (ref "U14") (pin "29") (pinfunction "PHYRSTB_29") (pintype "input"))
    )
    (net (code "85") (name "Net-(U14-REGOUT)") (class "Default")
      (node (ref "L5") (pin "2") (pinfunction "2_2") (pintype "passive"))
      (node (ref "U14") (pin "48") (pinfunction "REGOUT_48") (pintype "power_in"))
    )
    (net (code "86") (name "Net-(U14-VDDREG_1)") (class "Default")
      (node (ref "B9") (pin "1") (pinfunction "1_1") (pintype "passive"))
      (node (ref "C96") (pin "1") (pinfunction "1_1") (pintype "passive"))
      (node (ref "C97") (pin "1") (pinfunction "1_1") (pintype "passive"))
      (node (ref "C98") (pin "1") (pinfunction "1_1") (pintype "passive"))
      (node (ref "U14") (pin "44") (pinfunction "VDDREG_2_44") (pintype "power_in"))
      (node (ref "U14") (pin "45") (pinfunction "VDDREG_1_45") (pintype "power_in"))
    )
    (net (code "87") (name "Net-(U16-G)") (class "Default")
      (node (ref "R197") (pin "1") (pinfunction "1_1") (pintype "passive"))
      (node (ref "R200") (pin "2") (pinfunction "2_2") (pintype "passive"))
      (node (ref "U16") (pin "4") (pinfunction "G_4") (pintype "passive"))
    )
    (net (code "88") (name "unconnected-(JP3A-LVDS8-PadA14)") (class "Default")
      (node (ref "JP3") (pin "A14") (pinfunction "LVDS8_A14") (pintype "passive"))
    )
    (net (code "89") (name "unconnected-(JP3A-LVDS9-PadA15)") (class "Default")
      (node (ref "JP3") (pin "A15") (pinfunction "LVDS9_A15") (pintype "passive"))
    )
    (net (code "90") (name "unconnected-(JP3A-LVDS10-PadA16)") (class "Default")
      (node (ref "JP3") (pin "A16") (pinfunction "LVDS10_A16") (pintype "passive"))
    )
    (net (code "91") (name "unconnected-(JP3B-NC-PadB5)") (class "Default")
      (node (ref "JP3") (pin "B5") (pinfunction "NC_B5") (pintype "passive"))
    )
    (net (code "92") (name "unconnected-(JP3B-NC-PadB6)") (class "Default")
      (node (ref "JP3") (pin "B6") (pinfunction "NC_B6") (pintype "passive"))
    )
    (net (code "93") (name "unconnected-(JP3C-IO9-PadC4)") (class "Default")
      (node (ref "JP3") (pin "C4") (pinfunction "IO9_C4") (pintype "passive"))
    )
    (net (code "94") (name "unconnected-(JP3C-IO10-PadC5)") (class "Default")
      (node (ref "JP3") (pin "C5") (pinfunction "IO10_C5") (pintype "passive"))
    )
    (net (code "95") (name "unconnected-(JP3C-LVDSL7-PadC13)") (class "Default")
      (node (ref "JP3") (pin "C13") (pinfunction "LVDSL7_C13") (pintype "passive"))
    )
    (net (code "96") (name "unconnected-(JP3C-LVDSL8-PadC14)") (class "Default")
      (node (ref "JP3") (pin "C14") (pinfunction "LVDSL8_C14") (pintype "passive"))
    )
    (net (code "97") (name "unconnected-(JP3C-LVDSL9-PadC15)") (class "Default")
      (node (ref "JP3") (pin "C15") (pinfunction "LVDSL9_C15") (pintype "passive"))
    )
    (net (code "98") (name "unconnected-(JP3C-LVDSL10-PadC16)") (class "Default")
      (node (ref "JP3") (pin "C16") (pinfunction "LVDSL10_C16") (pintype "passive"))
    )
    (net (code "99") (name "unconnected-(U14-CKXTAL2-Pad43)") (class "Default")
      (node (ref "U14") (pin "43") (pinfunction "CKXTAL2_43") (pintype "output"))
    )
    (net (code "100") (name "unconnected-(U14-NC-Pad12)") (class "Default")
      (node (ref "U14") (pin "12") (pinfunction "NC_12") (pintype "passive"))
    )
  )
)
